# ProPrj_ElectronicSteatTagV6_2026-03-17.net
KiCad netlist of a schematic drawn in EasyEDA Pro
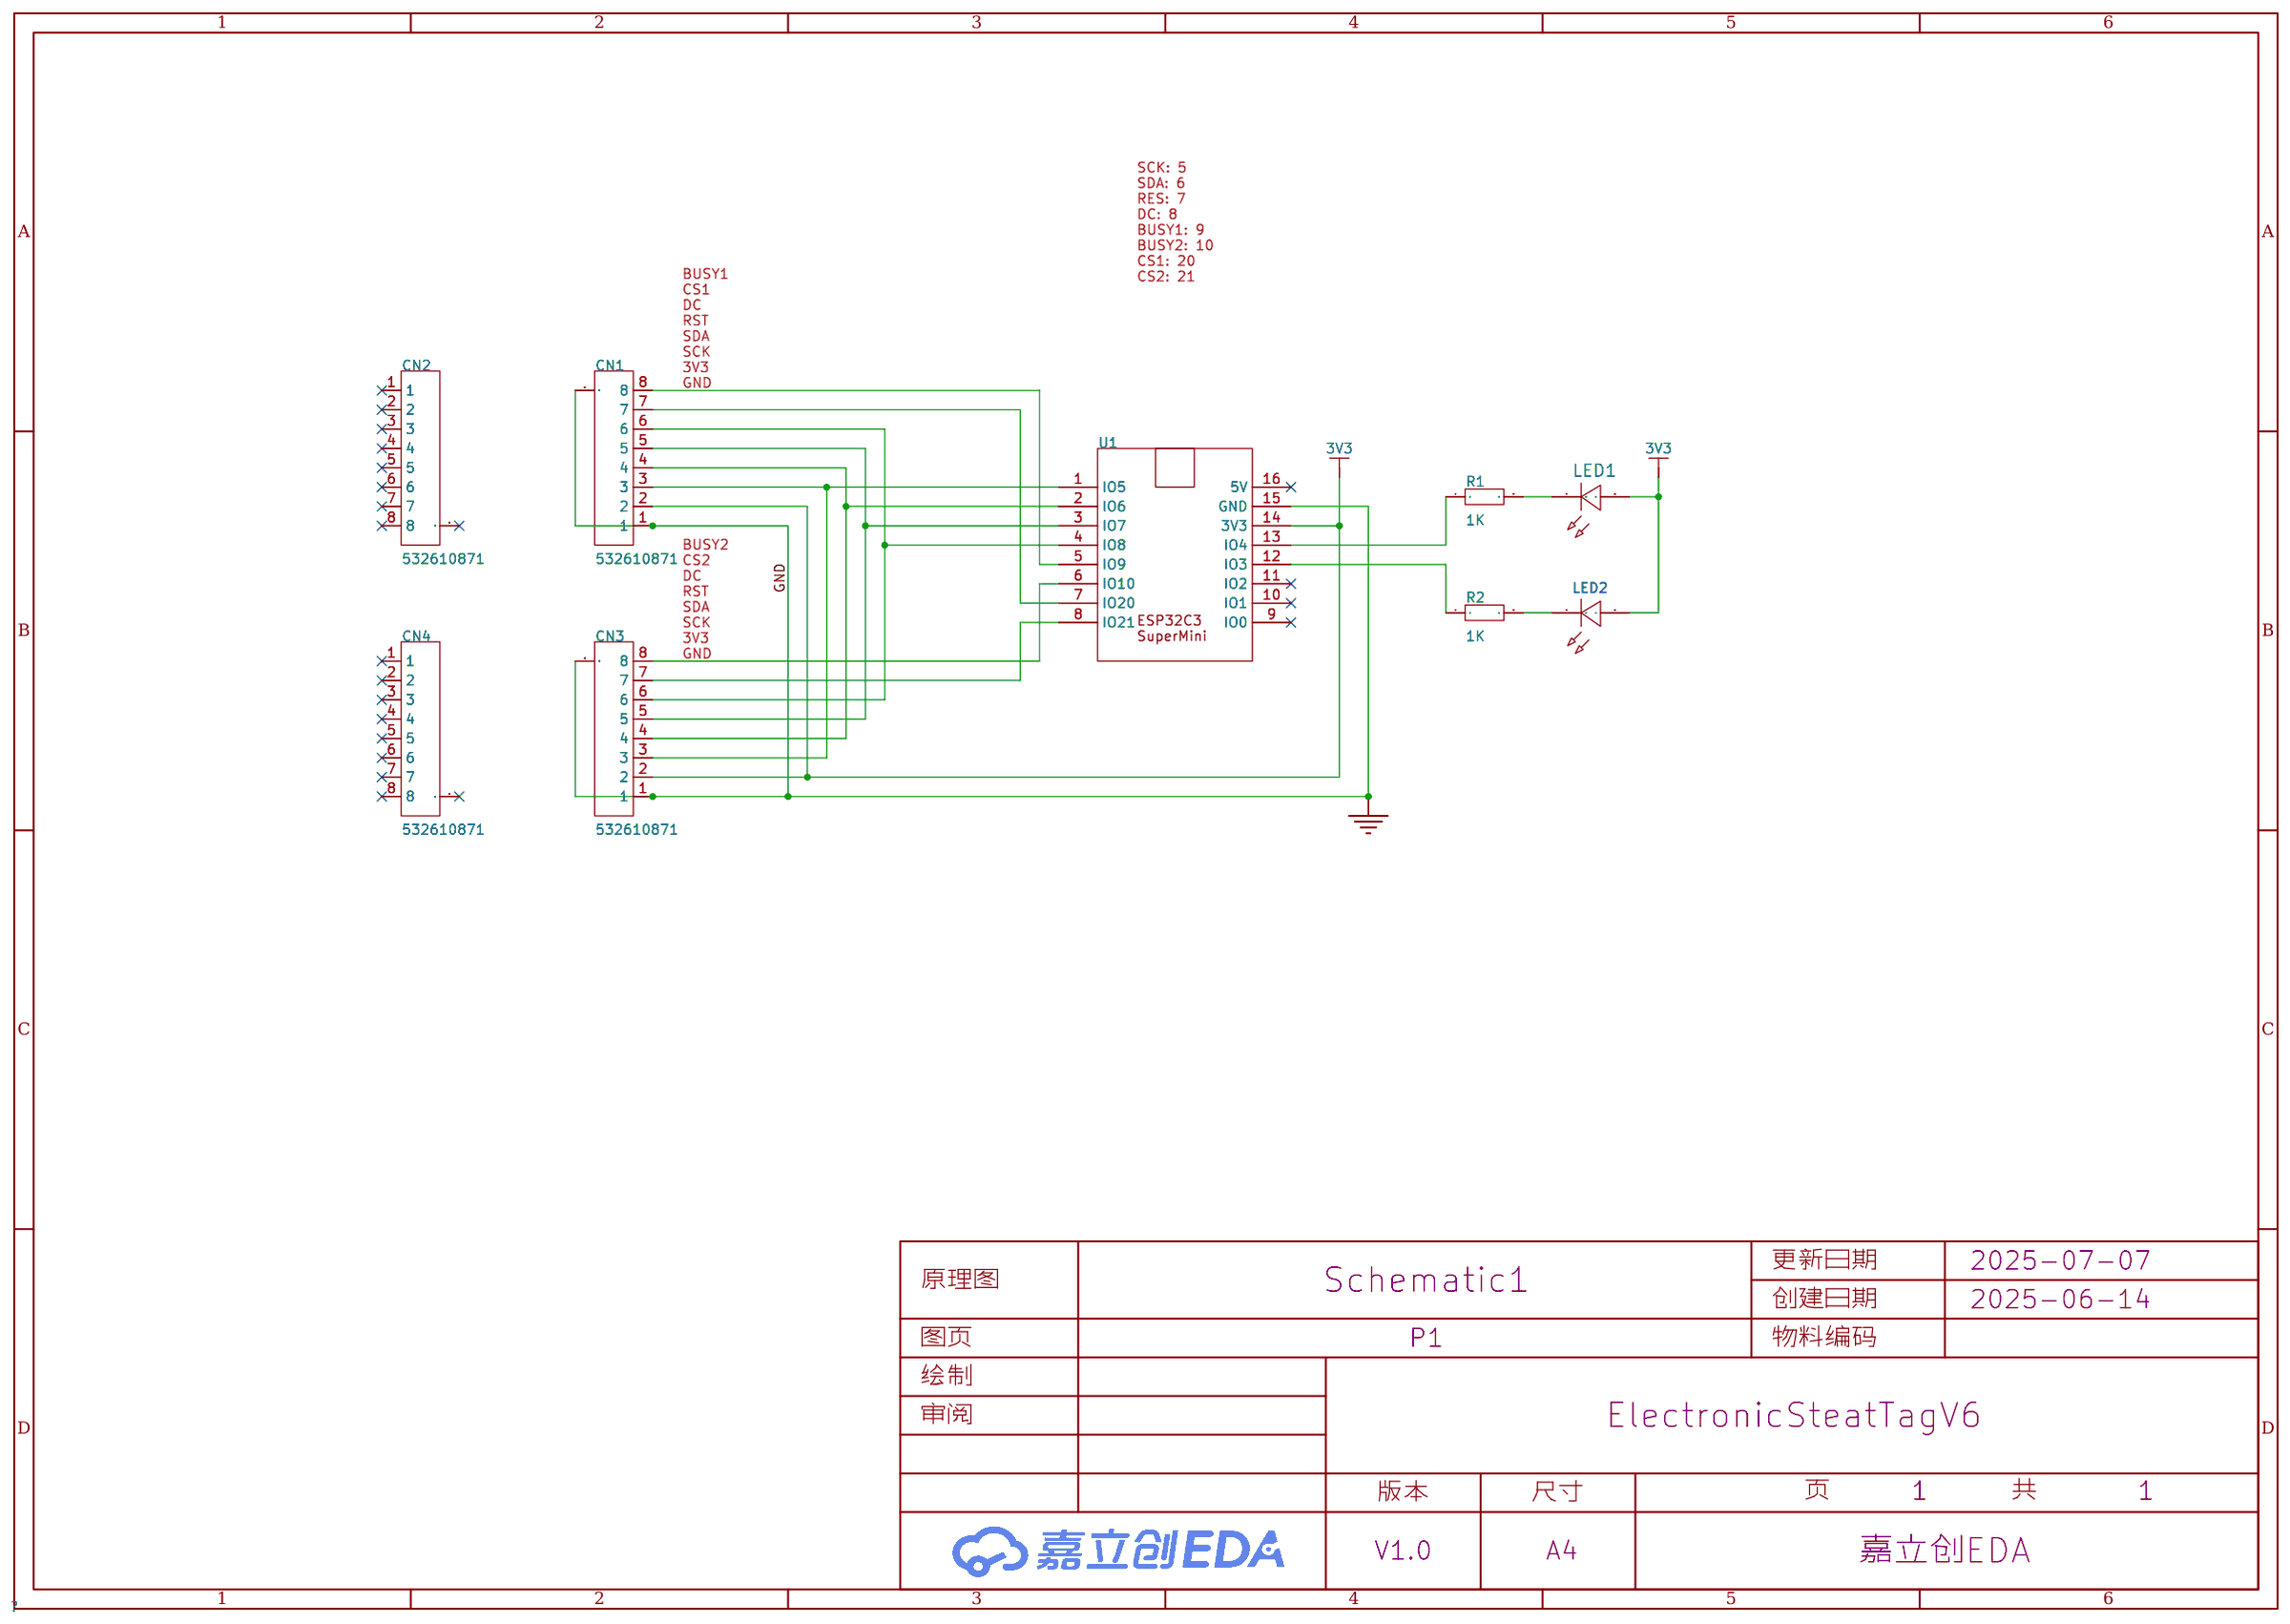
[diagram p0: schematic sheet]

(export (version "E")
  (design (tool "Eeschema 10.0.6"))
  (components
    (comp (ref "CN1")
      (value "532610871")
      (footprint "easyedapro:CONN-SMD_532610871")
      (fields (field (name "Manufacturer") "MOLEX"))
      (libsource (lib "easyedapro") (part "532610871"))
    )
    (comp (ref "CN2")
      (value "532610871")
      (footprint "easyedapro:CONN-SMD_532610871")
      (fields (field (name "Manufacturer") "MOLEX"))
      (libsource (lib "easyedapro") (part "532610871"))
    )
    (comp (ref "CN3")
      (value "532610871")
      (footprint "easyedapro:CONN-SMD_532610871")
      (fields (field (name "Manufacturer") "MOLEX"))
      (libsource (lib "easyedapro") (part "532610871"))
    )
    (comp (ref "CN4")
      (value "532610871")
      (footprint "easyedapro:CONN-SMD_532610871")
      (fields (field (name "Manufacturer") "MOLEX"))
      (libsource (lib "easyedapro") (part "532610871"))
    )
    (comp (ref "LED1")
      (value "~")
      (footprint "easyedapro:LED_0805")
      (libsource (lib "easyedapro") (part "LED_R"))
    )
    (comp (ref "LED2")
      (value "~")
      (footprint "easyedapro:LED_0805")
      (libsource (lib "easyedapro") (part "LED_B"))
    )
    (comp (ref "R1") (value "1K") (footprint "easyedapro:R0805") (libsource (lib "easyedapro") (part "电阻")))
    (comp (ref "R2") (value "1K") (footprint "easyedapro:R0805") (libsource (lib "easyedapro") (part "电阻")))
    (comp (ref "U1")
      (value "~")
      (footprint "easyedapro:ESP32C3SuperMini")
      (libsource (lib "easyedapro") (part "ESP32C3SuperMini"))
    )
  )
  (nets
    (net (code "1") (name "3V3") (class "Default")
      (node (ref "CN1") (pin "2") (pinfunction "2_2") (pintype "unspecified"))
      (node (ref "CN3") (pin "2") (pinfunction "2_2") (pintype "unspecified"))
      (node (ref "LED1") (pin "2") (pinfunction "A_2") (pintype "input"))
      (node (ref "LED2") (pin "2") (pinfunction "A_2") (pintype "input"))
      (node (ref "U1") (pin "14") (pinfunction "3V3_14") (pintype "input"))
    )
    (net (code "2") (name "GND") (class "Default")
      (node (ref "CN1") (pin "0") (pinfunction "0_0") (pintype "unspecified"))
      (node (ref "CN1") (pin "1") (pinfunction "1_1") (pintype "unspecified"))
      (node (ref "CN3") (pin "0") (pinfunction "0_0") (pintype "unspecified"))
      (node (ref "CN3") (pin "1") (pinfunction "1_1") (pintype "unspecified"))
      (node (ref "U1") (pin "15") (pinfunction "GND_15") (pintype "input"))
    )
    (net (code "3") (name "Net-(LED1-C)") (class "Default")
      (node (ref "LED1") (pin "1") (pinfunction "C_1") (pintype "input"))
      (node (ref "R1") (pin "2") (pinfunction "2_2") (pintype "input"))
    )
    (net (code "4") (name "Net-(LED2-C)") (class "Default")
      (node (ref "LED2") (pin "1") (pinfunction "C_1") (pintype "input"))
      (node (ref "R2") (pin "2") (pinfunction "2_2") (pintype "input"))
    )
    (net (code "5") (name "Net-(U1-IO3)") (class "Default")
      (node (ref "R2") (pin "1") (pinfunction "1_1") (pintype "input"))
      (node (ref "U1") (pin "12") (pinfunction "IO3_12") (pintype "input"))
    )
    (net (code "6") (name "Net-(U1-IO4)") (class "Default")
      (node (ref "R1") (pin "1") (pinfunction "1_1") (pintype "input"))
      (node (ref "U1") (pin "13") (pinfunction "IO4_13") (pintype "input"))
    )
    (net (code "7") (name "Net-(U1-IO5)") (class "Default")
      (node (ref "CN1") (pin "3") (pinfunction "3_3") (pintype "unspecified"))
      (node (ref "CN3") (pin "3") (pinfunction "3_3") (pintype "unspecified"))
      (node (ref "U1") (pin "1") (pinfunction "IO5_1") (pintype "input"))
    )
    (net (code "8") (name "Net-(U1-IO6)") (class "Default")
      (node (ref "CN1") (pin "4") (pinfunction "4_4") (pintype "unspecified"))
      (node (ref "CN3") (pin "4") (pinfunction "4_4") (pintype "unspecified"))
      (node (ref "U1") (pin "2") (pinfunction "IO6_2") (pintype "input"))
    )
    (net (code "9") (name "Net-(U1-IO7)") (class "Default")
      (node (ref "CN1") (pin "5") (pinfunction "5_5") (pintype "unspecified"))
      (node (ref "CN3") (pin "5") (pinfunction "5_5") (pintype "unspecified"))
      (node (ref "U1") (pin "3") (pinfunction "IO7_3") (pintype "input"))
    )
    (net (code "10") (name "Net-(U1-IO8)") (class "Default")
      (node (ref "CN1") (pin "6") (pinfunction "6_6") (pintype "unspecified"))
      (node (ref "CN3") (pin "6") (pinfunction "6_6") (pintype "unspecified"))
      (node (ref "U1") (pin "4") (pinfunction "IO8_4") (pintype "input"))
    )
    (net (code "11") (name "Net-(U1-IO9)") (class "Default")
      (node (ref "CN1") (pin "8") (pinfunction "8_8") (pintype "unspecified"))
      (node (ref "U1") (pin "5") (pinfunction "IO9_5") (pintype "input"))
    )
    (net (code "12") (name "Net-(U1-IO10)") (class "Default")
      (node (ref "CN3") (pin "8") (pinfunction "8_8") (pintype "unspecified"))
      (node (ref "U1") (pin "6") (pinfunction "IO10_6") (pintype "input"))
    )
    (net (code "13") (name "Net-(U1-IO20)") (class "Default")
      (node (ref "CN1") (pin "7") (pinfunction "7_7") (pintype "unspecified"))
      (node (ref "U1") (pin "7") (pinfunction "IO20_7") (pintype "input"))
    )
    (net (code "14") (name "Net-(U1-IO21)") (class "Default")
      (node (ref "CN3") (pin "7") (pinfunction "7_7") (pintype "unspecified"))
      (node (ref "U1") (pin "8") (pinfunction "IO21_8") (pintype "input"))
    )
    (net (code "15") (name "unconnected-(CN2-Pad0)") (class "Default")
      (node (ref "CN2") (pin "0") (pinfunction "0_0") (pintype "unspecified+no_connect"))
    )
    (net (code "16") (name "unconnected-(CN2-Pad1)") (class "Default")
      (node (ref "CN2") (pin "1") (pinfunction "1_1") (pintype "unspecified+no_connect"))
    )
    (net (code "17") (name "unconnected-(CN2-Pad2)") (class "Default")
      (node (ref "CN2") (pin "2") (pinfunction "2_2") (pintype "unspecified+no_connect"))
    )
    (net (code "18") (name "unconnected-(CN2-Pad3)") (class "Default")
      (node (ref "CN2") (pin "3") (pinfunction "3_3") (pintype "unspecified+no_connect"))
    )
    (net (code "19") (name "unconnected-(CN2-Pad4)") (class "Default")
      (node (ref "CN2") (pin "4") (pinfunction "4_4") (pintype "unspecified+no_connect"))
    )
    (net (code "20") (name "unconnected-(CN2-Pad5)") (class "Default")
      (node (ref "CN2") (pin "5") (pinfunction "5_5") (pintype "unspecified+no_connect"))
    )
    (net (code "21") (name "unconnected-(CN2-Pad6)") (class "Default")
      (node (ref "CN2") (pin "6") (pinfunction "6_6") (pintype "unspecified+no_connect"))
    )
    (net (code "22") (name "unconnected-(CN2-Pad7)") (class "Default")
      (node (ref "CN2") (pin "7") (pinfunction "7_7") (pintype "unspecified+no_connect"))
    )
    (net (code "23") (name "unconnected-(CN2-Pad8)") (class "Default")
      (node (ref "CN2") (pin "8") (pinfunction "8_8") (pintype "unspecified+no_connect"))
    )
    (net (code "24") (name "unconnected-(CN4-Pad0)") (class "Default")
      (node (ref "CN4") (pin "0") (pinfunction "0_0") (pintype "unspecified+no_connect"))
    )
    (net (code "25") (name "unconnected-(CN4-Pad1)") (class "Default")
      (node (ref "CN4") (pin "1") (pinfunction "1_1") (pintype "unspecified+no_connect"))
    )
    (net (code "26") (name "unconnected-(CN4-Pad2)") (class "Default")
      (node (ref "CN4") (pin "2") (pinfunction "2_2") (pintype "unspecified+no_connect"))
    )
    (net (code "27") (name "unconnected-(CN4-Pad3)") (class "Default")
      (node (ref "CN4") (pin "3") (pinfunction "3_3") (pintype "unspecified+no_connect"))
    )
    (net (code "28") (name "unconnected-(CN4-Pad4)") (class "Default")
      (node (ref "CN4") (pin "4") (pinfunction "4_4") (pintype "unspecified+no_connect"))
    )
    (net (code "29") (name "unconnected-(CN4-Pad5)") (class "Default")
      (node (ref "CN4") (pin "5") (pinfunction "5_5") (pintype "unspecified+no_connect"))
    )
    (net (code "30") (name "unconnected-(CN4-Pad6)") (class "Default")
      (node (ref "CN4") (pin "6") (pinfunction "6_6") (pintype "unspecified+no_connect"))
    )
    (net (code "31") (name "unconnected-(CN4-Pad7)") (class "Default")
      (node (ref "CN4") (pin "7") (pinfunction "7_7") (pintype "unspecified+no_connect"))
    )
    (net (code "32") (name "unconnected-(CN4-Pad8)") (class "Default")
      (node (ref "CN4") (pin "8") (pinfunction "8_8") (pintype "unspecified+no_connect"))
    )
    (net (code "33") (name "unconnected-(U1-5V-Pad16)") (class "Default")
      (node (ref "U1") (pin "16") (pinfunction "5V_16") (pintype "input+no_connect"))
    )
    (net (code "34") (name "unconnected-(U1-IO0-Pad9)") (class "Default")
      (node (ref "U1") (pin "9") (pinfunction "IO0_9") (pintype "input+no_connect"))
    )
    (net (code "35") (name "unconnected-(U1-IO1-Pad10)") (class "Default")
      (node (ref "U1") (pin "10") (pinfunction "IO1_10") (pintype "input+no_connect"))
    )
    (net (code "36") (name "unconnected-(U1-IO2-Pad11)") (class "Default")
      (node (ref "U1") (pin "11") (pinfunction "IO2_11") (pintype "input+no_connect"))
    )
  )
)
